# EngineControlCircuitSCH_Boyko.net
KiCad netlist of a schematic drawn in Altium Designer
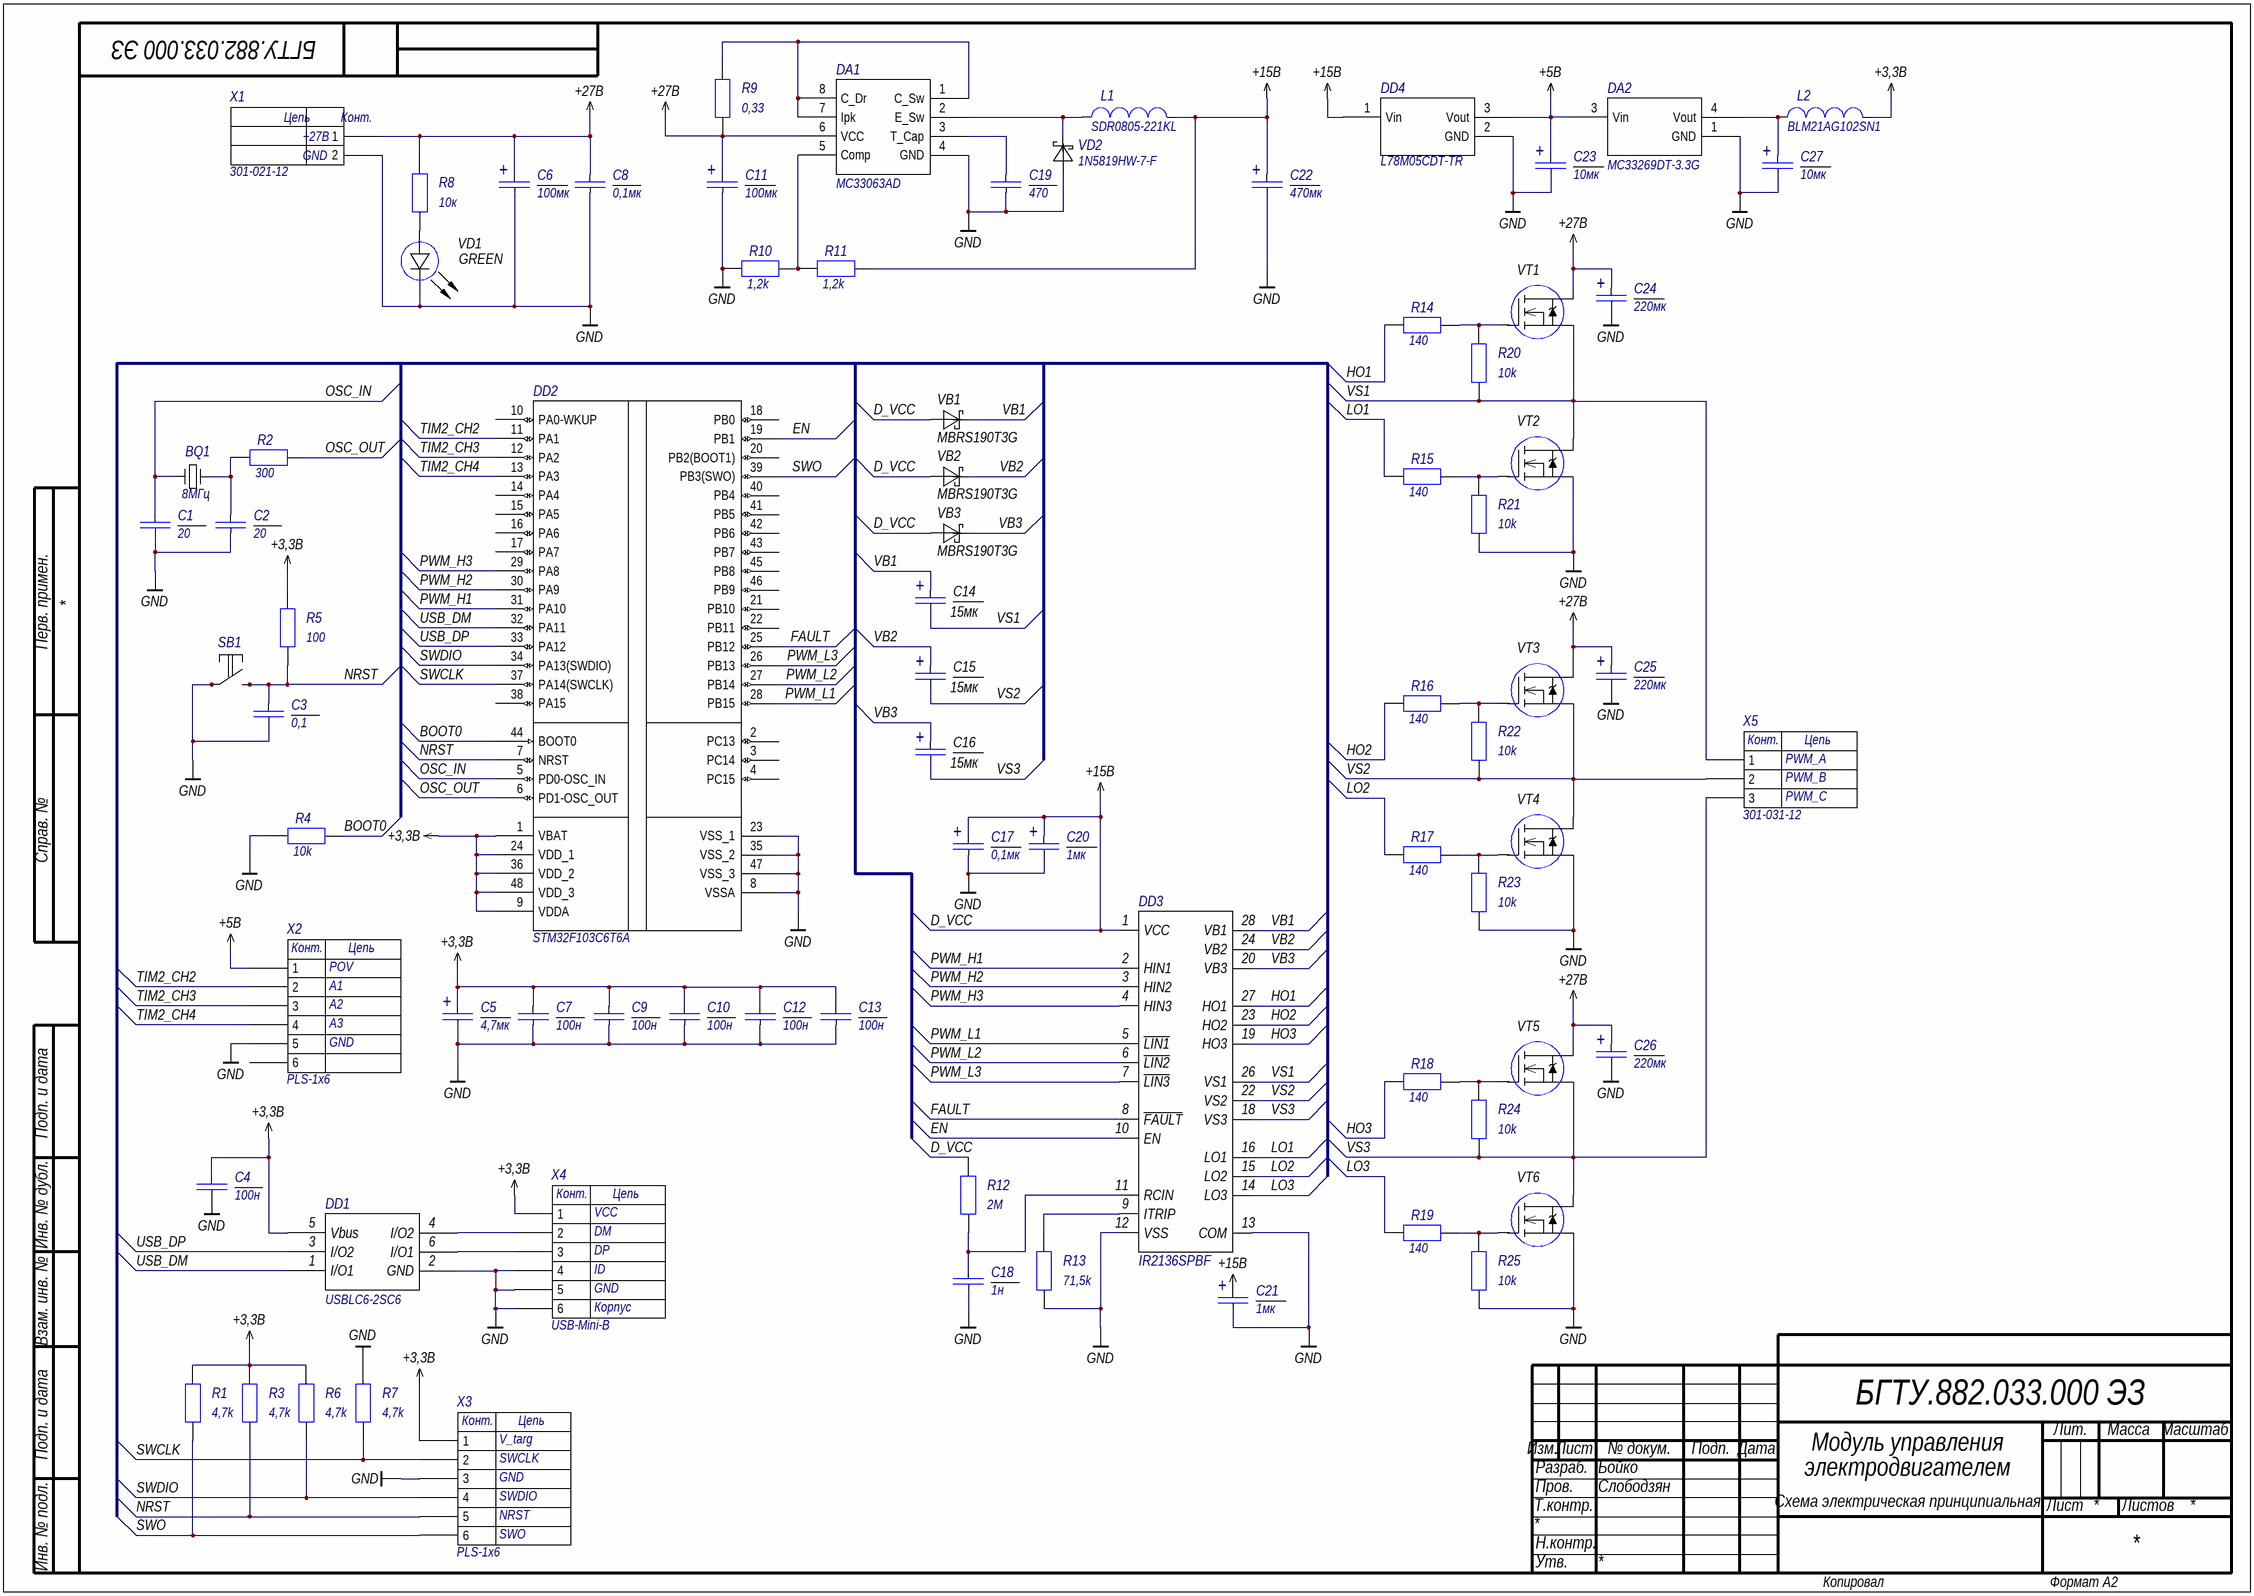
[diagram p0: EngineControlCircuitSCH_Boyko.SchDoc]

(export (version "E")
  (design (tool "Eeschema 10.0.6"))
  (components
    (comp (ref "BQ1")
      (value "8МГц")
      (footprint "OSC: 3225")
      (fields (field (name "VALUEMANUFACTURERPARTNUMBER") "SMD0503"))
      (libsource (lib "PassiveComps") (part "SMD0503"))
    )
    (comp (ref "C1")
      (value "20")
      (footprint "CAPC1608X90N")
      (description "Кер.ЧИП конд. 20пФ NPO 50В 5% 0603, GRM1885C1H200J")
      (fields (field (name "VALUEMANUFACTURERPARTNUMBER") " \"\" - "))
      (libsource (lib "PassiveComps") (part "Сapacitor"))
    )
    (comp (ref "C2")
      (value "20")
      (footprint "CAPC1608X90N")
      (description "Кер.ЧИП конд. 20пФ NPO 50В 5% 0603, GRM1885C1H200J")
      (fields (field (name "VALUEMANUFACTURERPARTNUMBER") " \"\" - "))
      (libsource (lib "PassiveComps") (part "Сapacitor"))
    )
    (comp (ref "C3")
      (value "0,1")
      (footprint "CAPC1005X55N")
      (description "04025A1R0BAT2A, Cap Ceramic 1pF 50V C0G 0.1pF Pad SMD 0402 125C T/R")
      (fields (field (name "VALUEMANUFACTURERPARTNUMBER") " \"\" - "))
      (libsource (lib "PassiveComps") (part "Сapacitor"))
    )
    (comp (ref "C4")
      (value "100н")
      (footprint "CAPC1005X55N")
      (description "Кер.чип.конд. 0402 X5R 100нФ 16В 10%, GRM155R61C104KA88D")
      (fields (field (name "VALUEMANUFACTURERPARTNUMBER") " \"\" - "))
      (libsource (lib "PassiveComps") (part "Сapacitor"))
    )
    (comp (ref "C5")
      (value "4,7мк")
      (footprint "CAP: TANTAL-B")
      (description "Конденсатор танталовый SMD 4,7uF 16V 20% case B")
      (fields (field (name "VALUEMANUFACTURERPARTNUMBER") " \"\" - "))
      (libsource (lib "PassiveComps") (part "Сapacitor_Pol"))
    )
    (comp (ref "C6")
      (value "100мк")
      (footprint "CAP: D6.3C2.5H11")
      (description "100мкф 35в 105° RD (6.3X11) конденсатор SAMWHA RD1V107M6L011BB")
      (fields (field (name "VALUEMANUFACTURERPARTNUMBER") "D \"D\" 27В-100мк 20%"))
      (libsource (lib "PassiveComps") (part "Сapacitor_Pol_1"))
    )
    (comp (ref "C7")
      (value "100н")
      (footprint "CAPC1005X55N")
      (description "Кер.чип.конд. 0402 X5R 100нФ 16В 10%, GRM155R61C104KA88D")
      (fields (field (name "VALUEMANUFACTURERPARTNUMBER") " \"\" - "))
      (libsource (lib "PassiveComps") (part "Сapacitor"))
    )
    (comp (ref "C8")
      (value "0,1мк")
      (footprint "CAPC2012X135N")
      (description "Кер.ЧИП конд. 0.1 мкФ Y5V 50В+80-20% 0805, GRM219F51H104Z")
      (fields (field (name "VALUEMANUFACTURERPARTNUMBER") " \"\" - "))
      (libsource (lib "PassiveComps") (part "Сapacitor"))
    )
    (comp (ref "C9")
      (value "100н")
      (footprint "CAPC1005X55N")
      (description "Кер.чип.конд. 0402 X5R 100нФ 16В 10%, GRM155R61C104KA88D")
      (fields (field (name "VALUEMANUFACTURERPARTNUMBER") " \"\" - "))
      (libsource (lib "PassiveComps") (part "Сapacitor"))
    )
    (comp (ref "C10")
      (value "100н")
      (footprint "CAPC1005X55N")
      (description "Кер.чип.конд. 0402 X5R 100нФ 16В 10%, GRM155R61C104KA88D")
      (fields (field (name "VALUEMANUFACTURERPARTNUMBER") " \"\" - "))
      (libsource (lib "PassiveComps") (part "Сapacitor"))
    )
    (comp (ref "C11")
      (value "100мк")
      (footprint "CAP: SMD D6.3A6.6H7.7")
      (description "107SML035M, CAP, 100UF, 35V, ALU ELEC, SMD")
      (fields (field (name "VALUEMANUFACTURERPARTNUMBER") " \"\" - "))
      (libsource (lib "PassiveComps") (part "Сapacitor_Pol"))
    )
    (comp (ref "C12")
      (value "100н")
      (footprint "CAPC1005X55N")
      (description "Кер.чип.конд. 0402 X5R 100нФ 16В 10%, GRM155R61C104KA88D")
      (fields (field (name "VALUEMANUFACTURERPARTNUMBER") " \"\" - "))
      (libsource (lib "PassiveComps") (part "Сapacitor"))
    )
    (comp (ref "C13")
      (value "100н")
      (footprint "CAPC1005X55N")
      (description "Кер.чип.конд. 0402 X5R 100нФ 16В 10%, GRM155R61C104KA88D")
      (fields (field (name "VALUEMANUFACTURERPARTNUMBER") " \"\" - "))
      (libsource (lib "PassiveComps") (part "Сapacitor"))
    )
    (comp (ref "C14")
      (value "15мк")
      (footprint "CAPMP7343X310N")
      (description "15мкф 16в SMD разм.C 10% тантал. конденсатор TAJC156K016RNJ")
      (libsource (lib "PassiveComps") (part "TAJC156K016RNJ"))
    )
    (comp (ref "C15")
      (value "15мк")
      (footprint "CAPMP7343X310N")
      (description "15мкф 16в SMD разм.C 10% тантал. конденсатор TAJC156K016RNJ")
      (libsource (lib "PassiveComps") (part "TAJC156K016RNJ"))
    )
    (comp (ref "C16")
      (value "15мк")
      (footprint "CAPMP7343X310N")
      (description "15мкф 16в SMD разм.C 10% тантал. конденсатор TAJC156K016RNJ")
      (libsource (lib "PassiveComps") (part "TAJC156K016RNJ"))
    )
    (comp (ref "C17")
      (value "0,1мк")
      (footprint "CAPMP3216X180N")
      (description "TECAP, 0.1 мкФ, 35 В, тип A, 10%, Конденсатор танталовый SMD")
      (fields (field (name "VALUEMANUFACTURERPARTNUMBER") "D \"D\" 27В-0,1мк 20%"))
      (libsource (lib "PassiveComps") (part "Сapacitor_Pol_1"))
    )
    (comp (ref "C18")
      (value "1н")
      (footprint "CAPC2012X135N")
      (description "Кер.ЧИП конд. 1000пФ X7R 50В,10%, 0805")
      (fields (field (name "VALUEMANUFACTURERPARTNUMBER") " \"\" - "))
      (libsource (lib "PassiveComps") (part "Сapacitor"))
    )
    (comp (ref "C19")
      (value "470")
      (footprint "CAPC1005X55N")
      (description "470пф X7R 50в 10% (0402) Чип керам,конденсатор MA0402XR471K500PRG")
      (fields (field (name "VALUEMANUFACTURERPARTNUMBER") " \"\" - "))
      (libsource (lib "PassiveComps") (part "Сapacitor"))
    )
    (comp (ref "C20")
      (value "1мк")
      (footprint "CAPMP3216X180N")
      (description "Сapacitor_Pol")
      (fields (field (name "VALUEMANUFACTURERPARTNUMBER") "D \"D\" 27В-1мк 20%"))
      (libsource (lib "PassiveComps") (part "Сapacitor_Pol_1"))
    )
    (comp (ref "C21")
      (value "1мк")
      (footprint "CAP: D5C2H11")
      (fields (field (name "VALUEMANUFACTURERPARTNUMBER") " \"\" - "))
      (libsource (lib "PassiveComps") (part "Сapacitor_Pol"))
    )
    (comp (ref "C22")
      (value "470мк")
      (footprint "CAP_ELEC_SIZE_G")
      (description "EEEFC1E471P, SMD эл-лит 25V 470uF /10*10.2/105°C")
      (fields (field (name "VALUEMANUFACTURERPARTNUMBER") " \"\" - "))
      (libsource (lib "PassiveComps") (part "Сapacitor_Pol"))
    )
    (comp (ref "C23")
      (value "10мк")
      (footprint "CAP: D5C2H11")
      (fields (field (name "VALUEMANUFACTURERPARTNUMBER") " \"\" - "))
      (libsource (lib "PassiveComps") (part "Сapacitor_Pol"))
    )
    (comp (ref "C24")
      (value "220мк")
      (footprint "WCAP-ATUL 8x11.5x3.5x0.5")
      (fields (field (name "VALUEMANUFACTURERPARTNUMBER") "D \"D\" 27В-220мк 20%"))
      (libsource (lib "PassiveComps") (part "Сapacitor_Pol_1"))
    )
    (comp (ref "C25")
      (value "220мк")
      (footprint "WCAP-ATUL 8x11.5x3.5x0.5")
      (fields (field (name "VALUEMANUFACTURERPARTNUMBER") "D \"D\" 27В-220мк 20%"))
      (libsource (lib "PassiveComps") (part "Сapacitor_Pol_1"))
    )
    (comp (ref "C26")
      (value "220мк")
      (footprint "WCAP-ATUL 8x11.5x3.5x0.5")
      (fields (field (name "VALUEMANUFACTURERPARTNUMBER") "D \"D\" 27В-220мк 20%"))
      (libsource (lib "PassiveComps") (part "Сapacitor_Pol_1"))
    )
    (comp (ref "C27")
      (value "10мк")
      (footprint "CAP: D5C2H11")
      (fields (field (name "VALUEMANUFACTURERPARTNUMBER") " \"\" - "))
      (libsource (lib "PassiveComps") (part "Сapacitor_Pol"))
    )
    (comp (ref "DA1")
      (value "MC33063AD")
      (footprint "8-SOIC-PAD")
      (description "Повышающий/ понижающий преобразователь напряжения [SO8] 1,5А")
      (libsource (lib "PowerDevices") (part "MC33063AD"))
    )
    (comp (ref "DA2")
      (value "MC33269DT-3.3G")
      (footprint "369A-13")
      (libsource (lib "PowerDevices") (part "MC33269DT-3.3G"))
    )
    (comp (ref "DD1")
      (value "USBLC6-2SC6")
      (footprint "SOT23-6")
      (libsource (lib "Interface") (part "USBLC6-2SC6"))
    )
    (comp (ref "DD2")
      (value "STM32F103C6T6A")
      (footprint "LQFP-48_N")
      (fields (field (name "PARTNUMBER") "STM32F103CBT6"))
      (libsource (lib "Microcontrollers") (part "STM32F103CBT6"))
    )
    (comp (ref "DD3")
      (value "IR2136SPBF")
      (footprint "SOIC127PX1032X265-28N")
      (fields (field (name "MF") "Infineon") (field (name "DIGI-KEY_PART_NUMBER") "IR2136SPBF-ND"))
      (libsource (lib "Driver") (part "IR2136SPBF"))
    )
    (comp (ref "DD4")
      (value "L78M05CDT-TR")
      (footprint "369A-13")
      (description "L78M05CDT-TR, Прецизионный регулятор напряжения, 500мА, 5В, [TO-252]")
      (libsource (lib "PowerDevices") (part "L78M05CDT-TR"))
    )
    (comp (ref "L1")
      (value "SDR0805-221KL")
      (footprint "IND: SDR0805")
      (description "SDR0805-221KL, 220 мкГн, Индуктивность SMD")
      (fields (field (name "VALUEMANUFACTURERPARTNUMBER") "B82477G4154M"))
      (libsource (lib "PassiveComps") (part "B82477G4154M"))
    )
    (comp (ref "L2")
      (value "BLM21AG102SN1")
      (footprint "IND: 0805")
      (description "Дроссель подавления ЭМП BLM21AG102SN1, 0805, Дроссель подавления ЭМП")
      (libsource (lib "PassiveComps") (part "BLM21AG102SN1"))
    )
    (comp (ref "R1")
      (value "4,7k")
      (footprint "RES0805")
      (description "0.125Вт 0805 4.7 кОм, 1%, Чип резистор (SMD) RC0805FR-074K7L")
      (fields (field (name "VALUEMANUFACTURERPARTNUMBER") " \"\" - "))
      (libsource (lib "PassiveComps") (part "Resistor"))
    )
    (comp (ref "R2")
      (value "300")
      (footprint "RES0402")
      (description "0.062Вт 0402 300 Ом, 1%, Чип резистор (SMD) RC0402FR-07300RL")
      (fields (field (name "VALUEMANUFACTURERPARTNUMBER") " \"\" -300 "))
      (libsource (lib "") (part "Resistor_1"))
    )
    (comp (ref "R3")
      (value "4,7k")
      (footprint "RES0805")
      (description "0.125Вт 0805 4.7 кОм, 1%, Чип резистор (SMD) RC0805FR-074K7L")
      (fields (field (name "VALUEMANUFACTURERPARTNUMBER") " \"\" - "))
      (libsource (lib "PassiveComps") (part "Resistor"))
    )
    (comp (ref "R4")
      (value "10k")
      (footprint "RES0805")
      (description "0.125Вт 0805 10 кОм, 5%, Чип резистор (SMD)")
      (fields (field (name "VALUEMANUFACTURERPARTNUMBER") " \"\" -10k "))
      (libsource (lib "") (part "Resistor_1"))
    )
    (comp (ref "R5")
      (value "100")
      (footprint "RES0805")
      (description "RC0402JR-07100RL")
      (fields (field (name "VALUEMANUFACTURERPARTNUMBER") " \"\" - "))
      (libsource (lib "PassiveComps") (part "Resistor"))
    )
    (comp (ref "R6")
      (value "4,7k")
      (footprint "RES0805")
      (description "0.125Вт 0805 4.7 кОм, 1%, Чип резистор (SMD) RC0805FR-074K7L")
      (fields (field (name "VALUEMANUFACTURERPARTNUMBER") " \"\" - "))
      (libsource (lib "PassiveComps") (part "Resistor"))
    )
    (comp (ref "R7")
      (value "4,7k")
      (footprint "RES0805")
      (description "0.125Вт 0805 4.7 кОм, 1%, Чип резистор (SMD) RC0805FR-074K7L")
      (fields (field (name "VALUEMANUFACTURERPARTNUMBER") " \"\" - "))
      (libsource (lib "PassiveComps") (part "Resistor"))
    )
    (comp (ref "R8")
      (value "10к")
      (footprint "RES0805")
      (description "Резистор RC0805JR-0710KL 0.125Вт 0805 10 кОм, 5%, Чип резистор (SMD)")
      (fields (field (name "VALUEMANUFACTURERPARTNUMBER") " \"\" - "))
      (libsource (lib "PassiveComps") (part "Resistor"))
    )
    (comp (ref "R9")
      (value "0,33")
      (footprint "RES1206")
      (description "0,33ом 5% RS-06 1/4W (1206) Чип резистор RS-06KR33JT")
      (fields (field (name "VALUEMANUFACTURERPARTNUMBER") " \"\" - "))
      (libsource (lib "PassiveComps") (part "Resistor"))
    )
    (comp (ref "R10")
      (value "1,2k")
      (footprint "RES0805")
      (description "Резистор постоянный SMD 0805 1,2K 5% / 0805S8J0122T5E")
      (fields (field (name "VALUEMANUFACTURERPARTNUMBER") " \"\" -300 "))
      (libsource (lib "") (part "Resistor_1"))
    )
    (comp (ref "R11")
      (value "1,2k")
      (footprint "RES0805")
      (description "Резистор постоянный SMD 0805 1,2K 5% / 0805S8J0122T5E")
      (fields (field (name "VALUEMANUFACTURERPARTNUMBER") " \"\" -300 "))
      (libsource (lib "") (part "Resistor_1"))
    )
    (comp (ref "R12")
      (value "2M")
      (footprint "RES0402")
      (description "0.062Вт 0402 2 МОм, 1%, Чип резистор (SMD)")
      (fields (field (name "VALUEMANUFACTURERPARTNUMBER") " \"\" - "))
      (libsource (lib "PassiveComps") (part "Resistor"))
    )
    (comp (ref "R13")
      (value "71,5k")
      (footprint "RES0805")
      (description "71,5 кОм 0805 1% CR05FL7-71K5 чип-резистор Viking tech")
      (fields (field (name "VALUEMANUFACTURERPARTNUMBER") " \"\" - "))
      (libsource (lib "PassiveComps") (part "Resistor"))
    )
    (comp (ref "R14")
      (value "140")
      (footprint "RES0805")
      (description "RC0805FR-07140RL, чип 0805 140 1%")
      (fields (field (name "VALUEMANUFACTURERPARTNUMBER") " \"\" -140 "))
      (libsource (lib "") (part "Resistor_1"))
    )
    (comp (ref "R15")
      (value "140")
      (footprint "RES0805")
      (description "RC0805FR-07140RL, чип 0805 140 1%")
      (fields (field (name "VALUEMANUFACTURERPARTNUMBER") " \"\" -140 "))
      (libsource (lib "") (part "Resistor_1"))
    )
    (comp (ref "R16")
      (value "140")
      (footprint "RES0805")
      (description "RC0805FR-07140RL, чип 0805 140 1%")
      (fields (field (name "VALUEMANUFACTURERPARTNUMBER") " \"\" -140 "))
      (libsource (lib "") (part "Resistor_1"))
    )
    (comp (ref "R17")
      (value "140")
      (footprint "RES0805")
      (description "RC0805FR-07140RL, чип 0805 140 1%")
      (fields (field (name "VALUEMANUFACTURERPARTNUMBER") " \"\" -140 "))
      (libsource (lib "") (part "Resistor_1"))
    )
    (comp (ref "R18")
      (value "140")
      (footprint "RES0805")
      (description "RC0805FR-07140RL, чип 0805 140 1%")
      (fields (field (name "VALUEMANUFACTURERPARTNUMBER") " \"\" -140 "))
      (libsource (lib "") (part "Resistor_1"))
    )
    (comp (ref "R19")
      (value "140")
      (footprint "RES0805")
      (description "RC0805FR-07140RL, чип 0805 140 1%")
      (fields (field (name "VALUEMANUFACTURERPARTNUMBER") " \"\" -140 "))
      (libsource (lib "") (part "Resistor_1"))
    )
    (comp (ref "R20")
      (value "10k")
      (footprint "RES0805")
      (description "RC0805FR-0710KL")
      (fields (field (name "VALUEMANUFACTURERPARTNUMBER") " \"\" - "))
      (libsource (lib "PassiveComps") (part "Resistor"))
    )
    (comp (ref "R21")
      (value "10k")
      (footprint "RES0805")
      (description "RC0805FR-0710KL")
      (fields (field (name "VALUEMANUFACTURERPARTNUMBER") " \"\" - "))
      (libsource (lib "PassiveComps") (part "Resistor"))
    )
    (comp (ref "R22")
      (value "10k")
      (footprint "RES0805")
      (description "RC0805FR-0710KL")
      (fields (field (name "VALUEMANUFACTURERPARTNUMBER") " \"\" - "))
      (libsource (lib "PassiveComps") (part "Resistor"))
    )
    (comp (ref "R23")
      (value "10k")
      (footprint "RES0805")
      (description "RC0805FR-0710KL")
      (fields (field (name "VALUEMANUFACTURERPARTNUMBER") " \"\" - "))
      (libsource (lib "PassiveComps") (part "Resistor"))
    )
    (comp (ref "R24")
      (value "10k")
      (footprint "RES0805")
      (description "RC0805FR-0710KL")
      (fields (field (name "VALUEMANUFACTURERPARTNUMBER") " \"\" - "))
      (libsource (lib "PassiveComps") (part "Resistor"))
    )
    (comp (ref "R25")
      (value "10k")
      (footprint "RES0805")
      (description "RC0805FR-0710KL")
      (fields (field (name "VALUEMANUFACTURERPARTNUMBER") " \"\" - "))
      (libsource (lib "PassiveComps") (part "Resistor"))
    )
    (comp (ref "SB1")
      (value "SWT-34")
      (footprint "SWT-34")
      (description "Тактовый переключатель SMD h=7мм (SDTM-630-N) (TS-06M-CSM)")
      (libsource (lib "PassiveComps") (part "SWT-34"))
    )
    (comp (ref "VB1")
      (value "MBRS190T3G")
      (footprint "DIODE: SMB")
      (description "Диод Шоттки 90В 1А MBRS190T3G, Диод Шоттки 90В 1А [SMB / DO-214AA]")
      (libsource (lib "PassiveComps") (part "MBRS190T3G"))
    )
    (comp (ref "VB2")
      (value "MBRS190T3G")
      (footprint "DIODE: SMB")
      (description "Диод Шоттки 90В 1А MBRS190T3G, Диод Шоттки 90В 1А [SMB / DO-214AA]")
      (libsource (lib "PassiveComps") (part "MBRS190T3G"))
    )
    (comp (ref "VB3")
      (value "MBRS190T3G")
      (footprint "DIODE: SMB")
      (description "Диод Шоттки 90В 1А MBRS190T3G, Диод Шоттки 90В 1А [SMB / DO-214AA]")
      (libsource (lib "PassiveComps") (part "MBRS190T3G"))
    )
    (comp (ref "VD1")
      (value "~")
      (footprint "LED: 0805G")
      (fields
        (field (name "VALUEMANUFACTURERPARTNUMBER") "LED, Green, *, *, *, -55...+150°C")
        (field (name "COLOR") "GREEN")
      )
      (libsource (lib "diode") (part "LED_single"))
    )
    (comp (ref "VD2")
      (value "1N5819HW-7-F")
      (footprint "DO-214AA")
      (description "Диод Шоттки 1N5819HW-7-F")
      (fields (field (name "VALUEMANUFACTURERPARTNUMBER") "SS24"))
      (libsource (lib "PassiveComps") (part "SS24"))
    )
    (comp (ref "VT1")
      (value "IRFZ14PBF")
      (footprint "TO220")
      (description "IRFZ14PBF, Транзистор, N-канал 60В 10А [TO-220AB]")
      (libsource (lib "Transistors") (part "IRFZ14PBF"))
    )
    (comp (ref "VT2")
      (value "IRFZ14PBF")
      (footprint "TO220")
      (description "IRFZ14PBF, Транзистор, N-канал 60В 10А [TO-220AB]")
      (libsource (lib "Transistors") (part "IRFZ14PBF"))
    )
    (comp (ref "VT3")
      (value "IRFZ14PBF")
      (footprint "TO220")
      (description "IRFZ14PBF, Транзистор, N-канал 60В 10А [TO-220AB]")
      (libsource (lib "Transistors") (part "IRFZ14PBF"))
    )
    (comp (ref "VT4")
      (value "IRFZ14PBF")
      (footprint "TO220")
      (description "IRFZ14PBF, Транзистор, N-канал 60В 10А [TO-220AB]")
      (libsource (lib "Transistors") (part "IRFZ14PBF"))
    )
    (comp (ref "VT5")
      (value "IRFZ14PBF")
      (footprint "TO220")
      (description "IRFZ14PBF, Транзистор, N-канал 60В 10А [TO-220AB]")
      (libsource (lib "Transistors") (part "IRFZ14PBF"))
    )
    (comp (ref "VT6")
      (value "IRFZ14PBF")
      (footprint "TO220")
      (description "IRFZ14PBF, Транзистор, N-канал 60В 10А [TO-220AB]")
      (libsource (lib "Transistors") (part "IRFZ14PBF"))
    )
    (comp (ref "X1")
      (value "301-021-12")
      (footprint "301-021-12_3D")
      (libsource (lib "Connectors") (part "301-021-12"))
    )
    (comp (ref "X2")
      (value "PLS-1x6")
      (footprint "CON: PLS-6")
      (description "PLS-6 (DS1021-1x6), Вилка штыревая 2.54мм 1x6 прямая тип1")
      (libsource (lib "Connectors") (part "PLS-1x6"))
    )
    (comp (ref "X3")
      (value "PLS-1x6")
      (footprint "CON: PLS-6")
      (description "PLS-6 (DS1021-1x6), Вилка штыревая 2.54мм 1x6 прямая тип1")
      (libsource (lib "Connectors") (part "PLS-1x6"))
    )
    (comp (ref "X4")
      (value "USB-Mini-B")
      (footprint "USB-MINI")
      (libsource (lib "Connectors") (part "USB-Mini-A"))
    )
    (comp (ref "X5")
      (value "301-031-12")
      (footprint "301-031-12_3D")
      (description "Клеммник винтовой, 3-контактный, 5мм, прямой")
      (libsource (lib "Connectors") (part "301-031-12"))
    )
  )
  (nets
    (net (code "1") (name "+3,3B") (class "Default")
      (node (ref "C10") (pin "1") (pinfunction "1_1") (pintype "passive"))
      (node (ref "C12") (pin "1") (pinfunction "1_1") (pintype "passive"))
      (node (ref "C13") (pin "1") (pinfunction "1_1") (pintype "passive"))
      (node (ref "C4") (pin "1") (pinfunction "1_1") (pintype "passive"))
      (node (ref "C5") (pin "1") (pinfunction "1_1") (pintype "passive"))
      (node (ref "C7") (pin "1") (pinfunction "1_1") (pintype "passive"))
      (node (ref "C9") (pin "1") (pinfunction "1_1") (pintype "passive"))
      (node (ref "DD1") (pin "5") (pinfunction "Vbus_5") (pintype "passive"))
      (node (ref "DD2") (pin "1") (pinfunction "VBAT_1") (pintype "power_in"))
      (node (ref "DD2") (pin "24") (pinfunction "VDD_1_24") (pintype "power_in"))
      (node (ref "DD2") (pin "36") (pinfunction "VDD_2_36") (pintype "power_in"))
      (node (ref "DD2") (pin "48") (pinfunction "VDD_3_48") (pintype "power_in"))
      (node (ref "DD2") (pin "9") (pinfunction "VDDA_9") (pintype "power_in"))
      (node (ref "L2") (pin "2") (pinfunction "2_2") (pintype "passive"))
      (node (ref "R1") (pin "1") (pinfunction "1_1") (pintype "passive"))
      (node (ref "R3") (pin "1") (pinfunction "1_1") (pintype "passive"))
      (node (ref "R5") (pin "1") (pinfunction "1_1") (pintype "passive"))
      (node (ref "R6") (pin "1") (pinfunction "1_1") (pintype "passive"))
      (node (ref "X3") (pin "1") (pinfunction "1_1") (pintype "passive"))
      (node (ref "X4") (pin "1") (pinfunction "1_1") (pintype "passive"))
    )
    (net (code "2") (name "+5B") (class "Default")
      (node (ref "C23") (pin "1") (pinfunction "1_1") (pintype "passive"))
      (node (ref "DA2") (pin "3") (pinfunction "Vin_3") (pintype "passive"))
      (node (ref "DD4") (pin "3") (pinfunction "Vout_3") (pintype "power_in"))
      (node (ref "X2") (pin "1") (pinfunction "1_1") (pintype "passive"))
    )
    (net (code "3") (name "+15B") (class "Default")
      (node (ref "C17") (pin "1") (pinfunction "1_1") (pintype "passive"))
      (node (ref "C20") (pin "1") (pinfunction "1_1") (pintype "passive"))
      (node (ref "C21") (pin "1") (pinfunction "1_1") (pintype "passive"))
      (node (ref "C22") (pin "1") (pinfunction "1_1") (pintype "passive"))
      (node (ref "DD3") (pin "1") (pinfunction "VCC_1") (pintype "passive"))
      (node (ref "DD4") (pin "1") (pinfunction "Vin_1") (pintype "passive"))
      (node (ref "L1") (pin "2") (pinfunction "2_2") (pintype "passive"))
      (node (ref "R11") (pin "2") (pinfunction "2_2") (pintype "passive"))
      (node (ref "R12") (pin "1") (pinfunction "1_1") (pintype "passive"))
      (node (ref "VB1") (pin "1") (pinfunction "1_1") (pintype "passive"))
      (node (ref "VB2") (pin "1") (pinfunction "1_1") (pintype "passive"))
      (node (ref "VB3") (pin "1") (pinfunction "1_1") (pintype "passive"))
    )
    (net (code "4") (name "+27B") (class "Default")
      (node (ref "C11") (pin "1") (pinfunction "1_1") (pintype "passive"))
      (node (ref "C24") (pin "1") (pinfunction "1_1") (pintype "passive"))
      (node (ref "C25") (pin "1") (pinfunction "1_1") (pintype "passive"))
      (node (ref "C26") (pin "1") (pinfunction "1_1") (pintype "passive"))
      (node (ref "C6") (pin "1") (pinfunction "1_1") (pintype "passive"))
      (node (ref "C8") (pin "1") (pinfunction "1_1") (pintype "passive"))
      (node (ref "DA1") (pin "6") (pinfunction "VCC_6") (pintype "power_in"))
      (node (ref "R8") (pin "1") (pinfunction "1_1") (pintype "passive"))
      (node (ref "R9") (pin "2") (pinfunction "2_2") (pintype "passive"))
      (node (ref "VT1") (pin "3") (pinfunction "3_3") (pintype "passive"))
      (node (ref "VT3") (pin "3") (pinfunction "3_3") (pintype "passive"))
      (node (ref "VT5") (pin "3") (pinfunction "3_3") (pintype "passive"))
      (node (ref "X1") (pin "1") (pinfunction "1_1") (pintype "passive"))
    )
    (net (code "5") (name "/BOOT0") (class "Default")
      (node (ref "DD2") (pin "44") (pinfunction "BOOT0_44") (pintype "input"))
      (node (ref "R4") (pin "2") (pinfunction "2_2") (pintype "passive"))
    )
    (net (code "6") (name "/EN") (class "Default")
      (node (ref "DD2") (pin "19") (pinfunction "PB1_19") (pintype "bidirectional"))
      (node (ref "DD3") (pin "10") (pinfunction "EN_10") (pintype "passive"))
    )
    (net (code "7") (name "/FAULT") (class "Default")
      (node (ref "DD2") (pin "25") (pinfunction "PB12_25") (pintype "bidirectional"))
      (node (ref "DD3") (pin "8") (pinfunction "~{FAULT}_8") (pintype "passive"))
    )
    (net (code "8") (name "/HO1") (class "Default")
      (node (ref "DD3") (pin "27") (pinfunction "HO1_27") (pintype "passive"))
      (node (ref "R14") (pin "1") (pinfunction "1_1") (pintype "passive"))
    )
    (net (code "9") (name "/HO2") (class "Default")
      (node (ref "DD3") (pin "23") (pinfunction "HO2_23") (pintype "passive"))
      (node (ref "R16") (pin "1") (pinfunction "1_1") (pintype "passive"))
    )
    (net (code "10") (name "/HO3") (class "Default")
      (node (ref "DD3") (pin "19") (pinfunction "HO3_19") (pintype "passive"))
      (node (ref "R18") (pin "1") (pinfunction "1_1") (pintype "passive"))
    )
    (net (code "11") (name "/LO1") (class "Default")
      (node (ref "DD3") (pin "16") (pinfunction "LO1_16") (pintype "passive"))
      (node (ref "R15") (pin "1") (pinfunction "1_1") (pintype "passive"))
    )
    (net (code "12") (name "/LO2") (class "Default")
      (node (ref "DD3") (pin "15") (pinfunction "LO2_15") (pintype "passive"))
      (node (ref "R17") (pin "1") (pinfunction "1_1") (pintype "passive"))
    )
    (net (code "13") (name "/LO3") (class "Default")
      (node (ref "DD3") (pin "14") (pinfunction "LO3_14") (pintype "passive"))
      (node (ref "R19") (pin "1") (pinfunction "1_1") (pintype "passive"))
    )
    (net (code "14") (name "/NRST") (class "Default")
      (node (ref "C3") (pin "1") (pinfunction "1_1") (pintype "passive"))
      (node (ref "DD2") (pin "7") (pinfunction "NRST_7") (pintype "bidirectional"))
      (node (ref "R3") (pin "2") (pinfunction "2_2") (pintype "passive"))
      (node (ref "R5") (pin "2") (pinfunction "2_2") (pintype "passive"))
      (node (ref "SB1") (pin "3") (pinfunction "3_3") (pintype "passive"))
      (node (ref "SB1") (pin "4") (pinfunction "4_4") (pintype "passive"))
      (node (ref "X3") (pin "5") (pinfunction "5_5") (pintype "passive"))
    )
    (net (code "15") (name "/OSC_IN") (class "Default")
      (node (ref "BQ1") (pin "1") (pinfunction "OSC1_1") (pintype "passive"))
      (node (ref "C1") (pin "1") (pinfunction "1_1") (pintype "passive"))
      (node (ref "DD2") (pin "5") (pinfunction "PD0-OSC_IN_5") (pintype "bidirectional"))
    )
    (net (code "16") (name "/OSC_OUT") (class "Default")
      (node (ref "DD2") (pin "6") (pinfunction "PD1-OSC_OUT_6") (pintype "bidirectional"))
      (node (ref "R2") (pin "2") (pinfunction "2_2") (pintype "passive"))
    )
    (net (code "17") (name "/PWM_H1") (class "Default")
      (node (ref "DD2") (pin "31") (pinfunction "PA10_31") (pintype "bidirectional"))
      (node (ref "DD3") (pin "2") (pinfunction "HIN1_2") (pintype "passive"))
    )
    (net (code "18") (name "/PWM_H2") (class "Default")
      (node (ref "DD2") (pin "30") (pinfunction "PA9_30") (pintype "bidirectional"))
      (node (ref "DD3") (pin "3") (pinfunction "HIN2_3") (pintype "passive"))
    )
    (net (code "19") (name "/PWM_H3") (class "Default")
      (node (ref "DD2") (pin "29") (pinfunction "PA8_29") (pintype "bidirectional"))
      (node (ref "DD3") (pin "4") (pinfunction "HIN3_4") (pintype "passive"))
    )
    (net (code "20") (name "/PWM_L1") (class "Default")
      (node (ref "DD2") (pin "28") (pinfunction "PB15_28") (pintype "bidirectional"))
      (node (ref "DD3") (pin "5") (pinfunction "~{LIN1}_5") (pintype "passive"))
    )
    (net (code "21") (name "/PWM_L2") (class "Default")
      (node (ref "DD2") (pin "27") (pinfunction "PB14_27") (pintype "bidirectional"))
      (node (ref "DD3") (pin "6") (pinfunction "~{LIN2}_6") (pintype "passive"))
    )
    (net (code "22") (name "/PWM_L3") (class "Default")
      (node (ref "DD2") (pin "26") (pinfunction "PB13_26") (pintype "bidirectional"))
      (node (ref "DD3") (pin "7") (pinfunction "~{LIN3}_7") (pintype "passive"))
    )
    (net (code "23") (name "/SWCLK") (class "Default")
      (node (ref "DD2") (pin "37") (pinfunction "PA14(SWCLK)_37") (pintype "bidirectional"))
      (node (ref "R7") (pin "2") (pinfunction "2_2") (pintype "passive"))
      (node (ref "X3") (pin "2") (pinfunction "2_2") (pintype "passive"))
    )
    (net (code "24") (name "/SWDIO") (class "Default")
      (node (ref "DD2") (pin "34") (pinfunction "PA13(SWDIO)_34") (pintype "bidirectional"))
      (node (ref "R6") (pin "2") (pinfunction "2_2") (pintype "passive"))
      (node (ref "X3") (pin "4") (pinfunction "4_4") (pintype "passive"))
    )
    (net (code "25") (name "/SWO") (class "Default")
      (node (ref "DD2") (pin "39") (pinfunction "PB3(SWO)_39") (pintype "bidirectional"))
      (node (ref "R1") (pin "2") (pinfunction "2_2") (pintype "passive"))
      (node (ref "X3") (pin "6") (pinfunction "6_6") (pintype "passive"))
    )
    (net (code "26") (name "/TIM2_CH2") (class "Default")
      (node (ref "DD2") (pin "11") (pinfunction "PA1_11") (pintype "bidirectional"))
      (node (ref "X2") (pin "2") (pinfunction "2_2") (pintype "passive"))
    )
    (net (code "27") (name "/TIM2_CH3") (class "Default")
      (node (ref "DD2") (pin "12") (pinfunction "PA2_12") (pintype "bidirectional"))
      (node (ref "X2") (pin "3") (pinfunction "3_3") (pintype "passive"))
    )
    (net (code "28") (name "/TIM2_CH4") (class "Default")
      (node (ref "DD2") (pin "13") (pinfunction "PA3_13") (pintype "bidirectional"))
      (node (ref "X2") (pin "4") (pinfunction "4_4") (pintype "passive"))
    )
    (net (code "29") (name "/USB_DM") (class "Default")
      (node (ref "DD1") (pin "1") (pinfunction "I/O1_1") (pintype "passive"))
      (node (ref "DD2") (pin "32") (pinfunction "PA11_32") (pintype "bidirectional"))
    )
    (net (code "30") (name "/USB_DP") (class "Default")
      (node (ref "DD1") (pin "3") (pinfunction "I/O2_3") (pintype "passive"))
      (node (ref "DD2") (pin "33") (pinfunction "PA12_33") (pintype "bidirectional"))
    )
    (net (code "31") (name "/VB1") (class "Default")
      (node (ref "C14") (pin "1") (pinfunction "1_1") (pintype "passive"))
      (node (ref "DD3") (pin "28") (pinfunction "VB1_28") (pintype "passive"))
      (node (ref "VB1") (pin "2") (pinfunction "2_2") (pintype "passive"))
    )
    (net (code "32") (name "/VB2") (class "Default")
      (node (ref "C15") (pin "1") (pinfunction "1_1") (pintype "passive"))
      (node (ref "DD3") (pin "24") (pinfunction "VB2_24") (pintype "passive"))
      (node (ref "VB2") (pin "2") (pinfunction "2_2") (pintype "passive"))
    )
    (net (code "33") (name "/VB3") (class "Default")
      (node (ref "C16") (pin "1") (pinfunction "1_1") (pintype "passive"))
      (node (ref "DD3") (pin "20") (pinfunction "VB3_20") (pintype "passive"))
      (node (ref "VB3") (pin "2") (pinfunction "2_2") (pintype "passive"))
    )
    (net (code "34") (name "/VS1") (class "Default")
      (node (ref "C14") (pin "2") (pinfunction "2_2") (pintype "passive"))
      (node (ref "DD3") (pin "26") (pinfunction "VS1_26") (pintype "passive"))
      (node (ref "R20") (pin "2") (pinfunction "2_2") (pintype "passive"))
      (node (ref "VT1") (pin "2") (pinfunction "2_2") (pintype "passive"))
      (node (ref "VT2") (pin "3") (pinfunction "3_3") (pintype "passive"))
      (node (ref "X5") (pin "1") (pinfunction "1_1") (pintype "passive"))
    )
    (net (code "35") (name "/VS2") (class "Default")
      (node (ref "C15") (pin "2") (pinfunction "2_2") (pintype "passive"))
      (node (ref "DD3") (pin "22") (pinfunction "VS2_22") (pintype "passive"))
      (node (ref "R22") (pin "2") (pinfunction "2_2") (pintype "passive"))
      (node (ref "VT3") (pin "2") (pinfunction "2_2") (pintype "passive"))
      (node (ref "VT4") (pin "3") (pinfunction "3_3") (pintype "passive"))
      (node (ref "X5") (pin "2") (pinfunction "2_2") (pintype "passive"))
    )
    (net (code "36") (name "/VS3") (class "Default")
      (node (ref "C16") (pin "2") (pinfunction "2_2") (pintype "passive"))
      (node (ref "DD3") (pin "18") (pinfunction "VS3_18") (pintype "passive"))
      (node (ref "R24") (pin "2") (pinfunction "2_2") (pintype "passive"))
      (node (ref "VT5") (pin "2") (pinfunction "2_2") (pintype "passive"))
      (node (ref "VT6") (pin "3") (pinfunction "3_3") (pintype "passive"))
      (node (ref "X5") (pin "3") (pinfunction "3_3") (pintype "passive"))
    )
    (net (code "37") (name "GND") (class "Default")
      (node (ref "C1") (pin "2") (pinfunction "2_2") (pintype "passive"))
      (node (ref "C10") (pin "2") (pinfunction "2_2") (pintype "passive"))
      (node (ref "C11") (pin "2") (pinfunction "2_2") (pintype "passive"))
      (node (ref "C12") (pin "2") (pinfunction "2_2") (pintype "passive"))
      (node (ref "C13") (pin "2") (pinfunction "2_2") (pintype "passive"))
      (node (ref "C17") (pin "2") (pinfunction "2_2") (pintype "passive"))
      (node (ref "C18") (pin "2") (pinfunction "2_2") (pintype "passive"))
      (node (ref "C19") (pin "2") (pinfunction "2_2") (pintype "passive"))
      (node (ref "C2") (pin "2") (pinfunction "2_2") (pintype "passive"))
      (node (ref "C20") (pin "2") (pinfunction "2_2") (pintype "passive"))
      (node (ref "C21") (pin "2") (pinfunction "2_2") (pintype "passive"))
      (node (ref "C22") (pin "2") (pinfunction "2_2") (pintype "passive"))
      (node (ref "C23") (pin "2") (pinfunction "2_2") (pintype "passive"))
      (node (ref "C24") (pin "2") (pinfunction "2_2") (pintype "passive"))
      (node (ref "C25") (pin "2") (pinfunction "2_2") (pintype "passive"))
      (node (ref "C26") (pin "2") (pinfunction "2_2") (pintype "passive"))
      (node (ref "C27") (pin "2") (pinfunction "2_2") (pintype "passive"))
      (node (ref "C3") (pin "2") (pinfunction "2_2") (pintype "passive"))
      (node (ref "C4") (pin "2") (pinfunction "2_2") (pintype "passive"))
      (node (ref "C5") (pin "2") (pinfunction "2_2") (pintype "passive"))
      (node (ref "C6") (pin "2") (pinfunction "2_2") (pintype "passive"))
      (node (ref "C7") (pin "2") (pinfunction "2_2") (pintype "passive"))
      (node (ref "C8") (pin "2") (pinfunction "2_2") (pintype "passive"))
      (node (ref "C9") (pin "2") (pinfunction "2_2") (pintype "passive"))
      (node (ref "DA1") (pin "4") (pinfunction "GND_4") (pintype "passive"))
      (node (ref "DA2") (pin "1") (pinfunction "GND_1") (pintype "passive"))
      (node (ref "DD1") (pin "2") (pinfunction "GND_2") (pintype "passive"))
      (node (ref "DD2") (pin "23") (pinfunction "VSS_1_23") (pintype "power_in"))
      (node (ref "DD2") (pin "35") (pinfunction "VSS_2_35") (pintype "power_in"))
      (node (ref "DD2") (pin "47") (pinfunction "VSS_3_47") (pintype "power_in"))
      (node (ref "DD2") (pin "8") (pinfunction "VSSA_8") (pintype "power_in"))
      (node (ref "DD3") (pin "12") (pinfunction "VSS_12") (pintype "passive"))
      (node (ref "DD3") (pin "13") (pinfunction "COM_13") (pintype "passive"))
      (node (ref "DD4") (pin "2") (pinfunction "GND_2") (pintype "passive"))
      (node (ref "R10") (pin "1") (pinfunction "1_1") (pintype "passive"))
      (node (ref "R13") (pin "2") (pinfunction "2_2") (pintype "passive"))
      (node (ref "R21") (pin "2") (pinfunction "2_2") (pintype "passive"))
      (node (ref "R23") (pin "2") (pinfunction "2_2") (pintype "passive"))
      (node (ref "R25") (pin "2") (pinfunction "2_2") (pintype "passive"))
      (node (ref "R4") (pin "1") (pinfunction "1_1") (pintype "passive"))
      (node (ref "R7") (pin "1") (pinfunction "1_1") (pintype "passive"))
      (node (ref "SB1") (pin "1") (pinfunction "1_1") (pintype "passive"))
      (node (ref "SB1") (pin "2") (pinfunction "2_2") (pintype "passive"))
      (node (ref "VD1") (pin "2") (pinfunction "C_2") (pintype "passive"))
      (node (ref "VD2") (pin "1") (pinfunction "1_1") (pintype "passive"))
      (node (ref "VT2") (pin "2") (pinfunction "2_2") (pintype "passive"))
      (node (ref "VT4") (pin "2") (pinfunction "2_2") (pintype "passive"))
      (node (ref "VT6") (pin "2") (pinfunction "2_2") (pintype "passive"))
      (node (ref "X1") (pin "2") (pinfunction "2_2") (pintype "passive"))
      (node (ref "X2") (pin "5") (pinfunction "5_5") (pintype "passive"))
      (node (ref "X3") (pin "3") (pinfunction "3_3") (pintype "passive"))
      (node (ref "X4") (pin "4") (pinfunction "4_4") (pintype "passive"))
      (node (ref "X4") (pin "5") (pinfunction "5_5") (pintype "passive"))
      (node (ref "X4") (pin "6") (pinfunction "6_6") (pintype "passive"))
    )
    (net (code "38") (name "Net-(BQ1-OSC2)") (class "Default")
      (node (ref "BQ1") (pin "3") (pinfunction "OSC2_3") (pintype "passive"))
      (node (ref "C2") (pin "1") (pinfunction "1_1") (pintype "passive"))
      (node (ref "R2") (pin "1") (pinfunction "1_1") (pintype "passive"))
    )
    (net (code "39") (name "Net-(DA1-C_Dr)") (class "Default")
      (node (ref "DA1") (pin "1") (pinfunction "C_Sw_1") (pintype "passive"))
      (node (ref "DA1") (pin "7") (pinfunction "Ipk_7") (pintype "passive"))
      (node (ref "DA1") (pin "8") (pinfunction "C_Dr_8") (pintype "power_in"))
      (node (ref "R9") (pin "1") (pinfunction "1_1") (pintype "passive"))
    )
    (net (code "40") (name "Net-(DA1-Comp)") (class "Default")
      (node (ref "DA1") (pin "5") (pinfunction "Comp_5") (pintype "power_in"))
      (node (ref "R10") (pin "2") (pinfunction "2_2") (pintype "passive"))
      (node (ref "R11") (pin "1") (pinfunction "1_1") (pintype "passive"))
    )
    (net (code "41") (name "Net-(DA1-E_Sw)") (class "Default")
      (node (ref "DA1") (pin "2") (pinfunction "E_Sw_2") (pintype "passive"))
      (node (ref "L1") (pin "1") (pinfunction "1_1") (pintype "passive"))
      (node (ref "VD2") (pin "2") (pinfunction "2_2") (pintype "passive"))
    )
    (net (code "42") (name "Net-(DA1-T_Cap)") (class "Default")
      (node (ref "C19") (pin "1") (pinfunction "1_1") (pintype "passive"))
      (node (ref "DA1") (pin "3") (pinfunction "T_Cap_3") (pintype "passive"))
    )
    (net (code "43") (name "Net-(DA2-Vout)") (class "Default")
      (node (ref "C27") (pin "1") (pinfunction "1_1") (pintype "passive"))
      (node (ref "DA2") (pin "4") (pinfunction "Vout_4") (pintype "power_in"))
      (node (ref "L2") (pin "1") (pinfunction "1_1") (pintype "passive"))
    )
    (net (code "44") (name "Net-(DD1-I{slash}O1-Pad6)") (class "Default")
      (node (ref "DD1") (pin "6") (pinfunction "I/O1_6") (pintype "power_in"))
      (node (ref "X4") (pin "3") (pinfunction "3_3") (pintype "passive"))
    )
    (net (code "45") (name "Net-(DD1-I{slash}O2-Pad4)") (class "Default")
      (node (ref "DD1") (pin "4") (pinfunction "I/O2_4") (pintype "power_in"))
      (node (ref "X4") (pin "2") (pinfunction "2_2") (pintype "passive"))
    )
    (net (code "46") (name "Net-(DD3-ITRIP)") (class "Default")
      (node (ref "DD3") (pin "9") (pinfunction "ITRIP_9") (pintype "passive"))
      (node (ref "R13") (pin "1") (pinfunction "1_1") (pintype "passive"))
    )
    (net (code "47") (name "Net-(DD3-RCIN)") (class "Default")
      (node (ref "C18") (pin "1") (pinfunction "1_1") (pintype "passive"))
      (node (ref "DD3") (pin "11") (pinfunction "RCIN_11") (pintype "passive"))
      (node (ref "R12") (pin "2") (pinfunction "2_2") (pintype "passive"))
    )
    (net (code "48") (name "Net-(R14-Pad2)") (class "Default")
      (node (ref "R14") (pin "2") (pinfunction "2_2") (pintype "passive"))
      (node (ref "R20") (pin "1") (pinfunction "1_1") (pintype "passive"))
      (node (ref "VT1") (pin "1") (pinfunction "1_1") (pintype "passive"))
    )
    (net (code "49") (name "Net-(R15-Pad2)") (class "Default")
      (node (ref "R15") (pin "2") (pinfunction "2_2") (pintype "passive"))
      (node (ref "R21") (pin "1") (pinfunction "1_1") (pintype "passive"))
      (node (ref "VT2") (pin "1") (pinfunction "1_1") (pintype "passive"))
    )
    (net (code "50") (name "Net-(R16-Pad2)") (class "Default")
      (node (ref "R16") (pin "2") (pinfunction "2_2") (pintype "passive"))
      (node (ref "R22") (pin "1") (pinfunction "1_1") (pintype "passive"))
      (node (ref "VT3") (pin "1") (pinfunction "1_1") (pintype "passive"))
    )
    (net (code "51") (name "Net-(R17-Pad2)") (class "Default")
      (node (ref "R17") (pin "2") (pinfunction "2_2") (pintype "passive"))
      (node (ref "R23") (pin "1") (pinfunction "1_1") (pintype "passive"))
      (node (ref "VT4") (pin "1") (pinfunction "1_1") (pintype "passive"))
    )
    (net (code "52") (name "Net-(R18-Pad2)") (class "Default")
      (node (ref "R18") (pin "2") (pinfunction "2_2") (pintype "passive"))
      (node (ref "R24") (pin "1") (pinfunction "1_1") (pintype "passive"))
      (node (ref "VT5") (pin "1") (pinfunction "1_1") (pintype "passive"))
    )
    (net (code "53") (name "Net-(R19-Pad2)") (class "Default")
      (node (ref "R19") (pin "2") (pinfunction "2_2") (pintype "passive"))
      (node (ref "R25") (pin "1") (pinfunction "1_1") (pintype "passive"))
      (node (ref "VT6") (pin "1") (pinfunction "1_1") (pintype "passive"))
    )
    (net (code "54") (name "Net-(VD1-A)") (class "Default")
      (node (ref "R8") (pin "2") (pinfunction "2_2") (pintype "passive"))
      (node (ref "VD1") (pin "1") (pinfunction "A_1") (pintype "passive"))
    )
    (net (code "55") (name "unconnected-(DD2-PA0-WKUP-Pad10)") (class "Default")
      (node (ref "DD2") (pin "10") (pinfunction "PA0-WKUP_10") (pintype "bidirectional"))
    )
    (net (code "56") (name "unconnected-(DD2-PA4-Pad14)") (class "Default")
      (node (ref "DD2") (pin "14") (pinfunction "PA4_14") (pintype "bidirectional"))
    )
    (net (code "57") (name "unconnected-(DD2-PA5-Pad15)") (class "Default")
      (node (ref "DD2") (pin "15") (pinfunction "PA5_15") (pintype "bidirectional"))
    )
    (net (code "58") (name "unconnected-(DD2-PA6-Pad16)") (class "Default")
      (node (ref "DD2") (pin "16") (pinfunction "PA6_16") (pintype "bidirectional"))
    )
    (net (code "59") (name "unconnected-(DD2-PA7-Pad17)") (class "Default")
      (node (ref "DD2") (pin "17") (pinfunction "PA7_17") (pintype "bidirectional"))
    )
    (net (code "60") (name "unconnected-(DD2-PA15-Pad38)") (class "Default")
      (node (ref "DD2") (pin "38") (pinfunction "PA15_38") (pintype "bidirectional"))
    )
    (net (code "61") (name "unconnected-(DD2-PB0-Pad18)") (class "Default")
      (node (ref "DD2") (pin "18") (pinfunction "PB0_18") (pintype "bidirectional"))
    )
    (net (code "62") (name "unconnected-(DD2-PB2(BOOT1)-Pad20)") (class "Default")
      (node (ref "DD2") (pin "20") (pinfunction "PB2(BOOT1)_20") (pintype "bidirectional"))
    )
    (net (code "63") (name "unconnected-(DD2-PB4-Pad40)") (class "Default")
      (node (ref "DD2") (pin "40") (pinfunction "PB4_40") (pintype "bidirectional"))
    )
    (net (code "64") (name "unconnected-(DD2-PB5-Pad41)") (class "Default")
      (node (ref "DD2") (pin "41") (pinfunction "PB5_41") (pintype "bidirectional"))
    )
    (net (code "65") (name "unconnected-(DD2-PB6-Pad42)") (class "Default")
      (node (ref "DD2") (pin "42") (pinfunction "PB6_42") (pintype "bidirectional"))
    )
    (net (code "66") (name "unconnected-(DD2-PB7-Pad43)") (class "Default")
      (node (ref "DD2") (pin "43") (pinfunction "PB7_43") (pintype "bidirectional"))
    )
    (net (code "67") (name "unconnected-(DD2-PB8-Pad45)") (class "Default")
      (node (ref "DD2") (pin "45") (pinfunction "PB8_45") (pintype "bidirectional"))
    )
    (net (code "68") (name "unconnected-(DD2-PB9-Pad46)") (class "Default")
      (node (ref "DD2") (pin "46") (pinfunction "PB9_46") (pintype "bidirectional"))
    )
    (net (code "69") (name "unconnected-(DD2-PB10-Pad21)") (class "Default")
      (node (ref "DD2") (pin "21") (pinfunction "PB10_21") (pintype "bidirectional"))
    )
    (net (code "70") (name "unconnected-(DD2-PB11-Pad22)") (class "Default")
      (node (ref "DD2") (pin "22") (pinfunction "PB11_22") (pintype "bidirectional"))
    )
    (net (code "71") (name "unconnected-(DD2-PC13-Pad2)") (class "Default")
      (node (ref "DD2") (pin "2") (pinfunction "PC13_2") (pintype "bidirectional"))
    )
    (net (code "72") (name "unconnected-(DD2-PC14-Pad3)") (class "Default")
      (node (ref "DD2") (pin "3") (pinfunction "PC14_3") (pintype "bidirectional"))
    )
    (net (code "73") (name "unconnected-(DD2-PC15-Pad4)") (class "Default")
      (node (ref "DD2") (pin "4") (pinfunction "PC15_4") (pintype "bidirectional"))
    )
    (net (code "74") (name "unconnected-(X2-Pad6)") (class "Default")
      (node (ref "X2") (pin "6") (pinfunction "6_6") (pintype "passive"))
    )
  )
)
